# switches_LEDs.net
KiCad netlist of a schematic drawn in Altium Designer
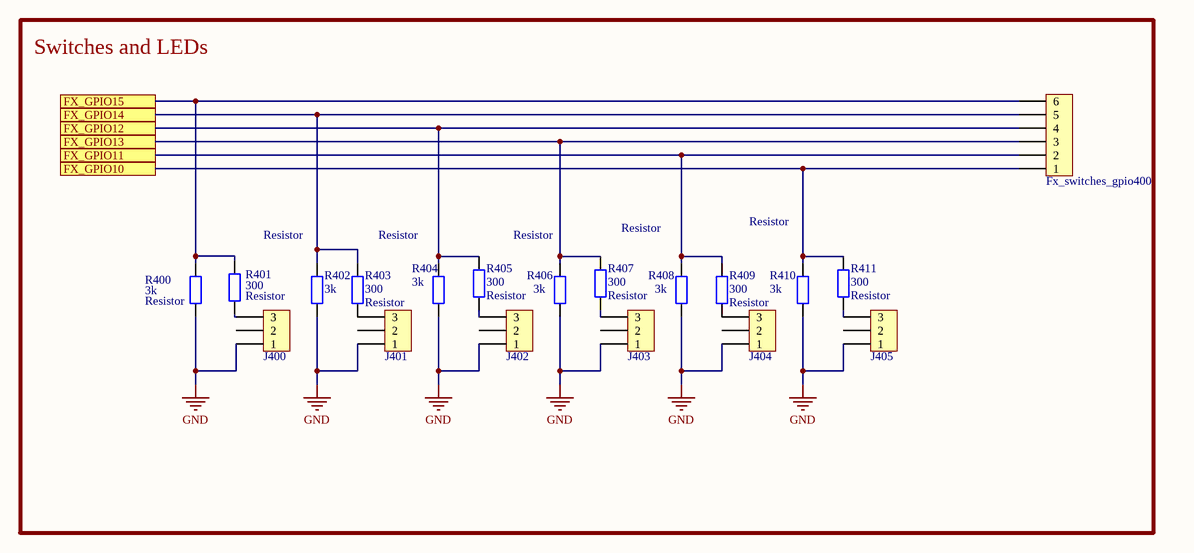
[diagram p0: switches_LEDs.SchDoc]

(export (version "E")
  (design (tool "Eeschema 10.0.6"))
  (components
    (comp (ref "Fx_switches_gpio400")
      (value "Header 1x6")
      (footprint "Header 1x6")
      (libsource (lib "AAURacing") (part "Header 1x6"))
    )
    (comp (ref "J400")
      (value "Header 1x3")
      (footprint "Header 1x3")
      (libsource (lib "AAURacing") (part "Header 1x3"))
    )
    (comp (ref "J401")
      (value "Header 1x3")
      (footprint "Header 1x3")
      (libsource (lib "AAURacing") (part "Header 1x3"))
    )
    (comp (ref "J402")
      (value "Header 1x3")
      (footprint "Header 1x3")
      (libsource (lib "AAURacing") (part "Header 1x3"))
    )
    (comp (ref "J403")
      (value "Header 1x3")
      (footprint "Header 1x3")
      (libsource (lib "AAURacing") (part "Header 1x3"))
    )
    (comp (ref "J404")
      (value "Header 1x3")
      (footprint "Header 1x3")
      (libsource (lib "AAURacing") (part "Header 1x3"))
    )
    (comp (ref "J405")
      (value "Header 1x3")
      (footprint "Header 1x3")
      (libsource (lib "AAURacing") (part "Header 1x3"))
    )
    (comp (ref "R400")
      (value "Resistor")
      (footprint "RES THT 9mm")
      (fields (field (name "ALTIUM_VALUE") "3k"))
      (libsource (lib "AAURacing") (part "Resistor"))
    )
    (comp (ref "R401")
      (value "Resistor")
      (footprint "RES THT 9mm")
      (fields (field (name "ALTIUM_VALUE") "300"))
      (libsource (lib "AAURacing") (part "Resistor"))
    )
    (comp (ref "R402")
      (value "Resistor")
      (footprint "RES THT 9mm")
      (fields (field (name "ALTIUM_VALUE") "3k"))
      (libsource (lib "AAURacing") (part "Resistor"))
    )
    (comp (ref "R403")
      (value "Resistor")
      (footprint "RES THT 9mm")
      (fields (field (name "ALTIUM_VALUE") "300"))
      (libsource (lib "AAURacing") (part "Resistor"))
    )
    (comp (ref "R404")
      (value "Resistor")
      (footprint "RES THT 9mm")
      (fields (field (name "ALTIUM_VALUE") "3k"))
      (libsource (lib "AAURacing") (part "Resistor"))
    )
    (comp (ref "R405")
      (value "Resistor")
      (footprint "RES THT 9mm")
      (fields (field (name "ALTIUM_VALUE") "300"))
      (libsource (lib "AAURacing") (part "Resistor"))
    )
    (comp (ref "R406")
      (value "Resistor")
      (footprint "RES THT 9mm")
      (fields (field (name "ALTIUM_VALUE") "3k"))
      (libsource (lib "AAURacing") (part "Resistor"))
    )
    (comp (ref "R407")
      (value "Resistor")
      (footprint "RES THT 9mm")
      (fields (field (name "ALTIUM_VALUE") "300"))
      (libsource (lib "AAURacing") (part "Resistor"))
    )
    (comp (ref "R408")
      (value "Resistor")
      (footprint "RES THT 9mm")
      (fields (field (name "ALTIUM_VALUE") "3k"))
      (libsource (lib "AAURacing") (part "Resistor"))
    )
    (comp (ref "R409")
      (value "Resistor")
      (footprint "RES THT 9mm")
      (fields (field (name "ALTIUM_VALUE") "300"))
      (libsource (lib "AAURacing") (part "Resistor"))
    )
    (comp (ref "R410")
      (value "Resistor")
      (footprint "RES THT 9mm")
      (fields (field (name "ALTIUM_VALUE") "3k"))
      (libsource (lib "AAURacing") (part "Resistor"))
    )
    (comp (ref "R411")
      (value "Resistor")
      (footprint "RES THT 9mm")
      (fields (field (name "ALTIUM_VALUE") "300"))
      (libsource (lib "AAURacing") (part "Resistor"))
    )
  )
  (nets
    (net (code "1") (name "/FX_GPIO10") (class "Default")
      (node (ref "Fx_switches_gpio400") (pin "1") (pinfunction "1_1") (pintype "passive"))
      (node (ref "R410") (pin "2") (pinfunction "2_2") (pintype "passive"))
      (node (ref "R411") (pin "2") (pinfunction "2_2") (pintype "passive"))
    )
    (net (code "2") (name "/FX_GPIO11") (class "Default")
      (node (ref "Fx_switches_gpio400") (pin "2") (pinfunction "2_2") (pintype "passive"))
      (node (ref "R408") (pin "2") (pinfunction "2_2") (pintype "passive"))
      (node (ref "R409") (pin "2") (pinfunction "2_2") (pintype "passive"))
    )
    (net (code "3") (name "/FX_GPIO12") (class "Default")
      (node (ref "Fx_switches_gpio400") (pin "4") (pinfunction "4_4") (pintype "passive"))
      (node (ref "R404") (pin "2") (pinfunction "2_2") (pintype "passive"))
      (node (ref "R405") (pin "2") (pinfunction "2_2") (pintype "passive"))
    )
    (net (code "4") (name "/FX_GPIO13") (class "Default")
      (node (ref "Fx_switches_gpio400") (pin "3") (pinfunction "3_3") (pintype "passive"))
      (node (ref "R406") (pin "2") (pinfunction "2_2") (pintype "passive"))
      (node (ref "R407") (pin "2") (pinfunction "2_2") (pintype "passive"))
    )
    (net (code "5") (name "/FX_GPIO14") (class "Default")
      (node (ref "Fx_switches_gpio400") (pin "5") (pinfunction "5_5") (pintype "passive"))
      (node (ref "R402") (pin "2") (pinfunction "2_2") (pintype "passive"))
      (node (ref "R403") (pin "2") (pinfunction "2_2") (pintype "passive"))
    )
    (net (code "6") (name "/FX_GPIO15") (class "Default")
      (node (ref "Fx_switches_gpio400") (pin "6") (pinfunction "6_6") (pintype "passive"))
      (node (ref "R400") (pin "2") (pinfunction "2_2") (pintype "passive"))
      (node (ref "R401") (pin "2") (pinfunction "2_2") (pintype "passive"))
    )
    (net (code "7") (name "GND") (class "Default")
      (node (ref "J400") (pin "1") (pinfunction "1_1") (pintype "passive"))
      (node (ref "J401") (pin "1") (pinfunction "1_1") (pintype "passive"))
      (node (ref "J402") (pin "1") (pinfunction "1_1") (pintype "passive"))
      (node (ref "J403") (pin "1") (pinfunction "1_1") (pintype "passive"))
      (node (ref "J404") (pin "1") (pinfunction "1_1") (pintype "passive"))
      (node (ref "J405") (pin "1") (pinfunction "1_1") (pintype "passive"))
      (node (ref "R400") (pin "1") (pinfunction "1_1") (pintype "passive"))
      (node (ref "R402") (pin "1") (pinfunction "1_1") (pintype "passive"))
      (node (ref "R404") (pin "1") (pinfunction "1_1") (pintype "passive"))
      (node (ref "R406") (pin "1") (pinfunction "1_1") (pintype "passive"))
      (node (ref "R408") (pin "1") (pinfunction "1_1") (pintype "passive"))
      (node (ref "R410") (pin "1") (pinfunction "1_1") (pintype "passive"))
    )
    (net (code "8") (name "Net-(J400-Pad3)") (class "Default")
      (node (ref "J400") (pin "3") (pinfunction "3_3") (pintype "passive"))
      (node (ref "R401") (pin "1") (pinfunction "1_1") (pintype "passive"))
    )
    (net (code "9") (name "Net-(J401-Pad3)") (class "Default")
      (node (ref "J401") (pin "3") (pinfunction "3_3") (pintype "passive"))
      (node (ref "R403") (pin "1") (pinfunction "1_1") (pintype "passive"))
    )
    (net (code "10") (name "Net-(J402-Pad3)") (class "Default")
      (node (ref "J402") (pin "3") (pinfunction "3_3") (pintype "passive"))
      (node (ref "R405") (pin "1") (pinfunction "1_1") (pintype "passive"))
    )
    (net (code "11") (name "Net-(J403-Pad3)") (class "Default")
      (node (ref "J403") (pin "3") (pinfunction "3_3") (pintype "passive"))
      (node (ref "R407") (pin "1") (pinfunction "1_1") (pintype "passive"))
    )
    (net (code "12") (name "Net-(J404-Pad3)") (class "Default")
      (node (ref "J404") (pin "3") (pinfunction "3_3") (pintype "passive"))
      (node (ref "R409") (pin "1") (pinfunction "1_1") (pintype "passive"))
    )
    (net (code "13") (name "Net-(J405-Pad3)") (class "Default")
      (node (ref "J405") (pin "3") (pinfunction "3_3") (pintype "passive"))
      (node (ref "R411") (pin "1") (pinfunction "1_1") (pintype "passive"))
    )
    (net (code "14") (name "unconnected-(J400-Pad2)") (class "Default")
      (node (ref "J400") (pin "2") (pinfunction "2_2") (pintype "passive"))
    )
    (net (code "15") (name "unconnected-(J401-Pad2)") (class "Default")
      (node (ref "J401") (pin "2") (pinfunction "2_2") (pintype "passive"))
    )
    (net (code "16") (name "unconnected-(J402-Pad2)") (class "Default")
      (node (ref "J402") (pin "2") (pinfunction "2_2") (pintype "passive"))
    )
    (net (code "17") (name "unconnected-(J403-Pad2)") (class "Default")
      (node (ref "J403") (pin "2") (pinfunction "2_2") (pintype "passive"))
    )
    (net (code "18") (name "unconnected-(J404-Pad2)") (class "Default")
      (node (ref "J404") (pin "2") (pinfunction "2_2") (pintype "passive"))
    )
    (net (code "19") (name "unconnected-(J405-Pad2)") (class "Default")
      (node (ref "J405") (pin "2") (pinfunction "2_2") (pintype "passive"))
    )
  )
)
